# M115D.net
KiCad netlist of a schematic drawn in EAGLE
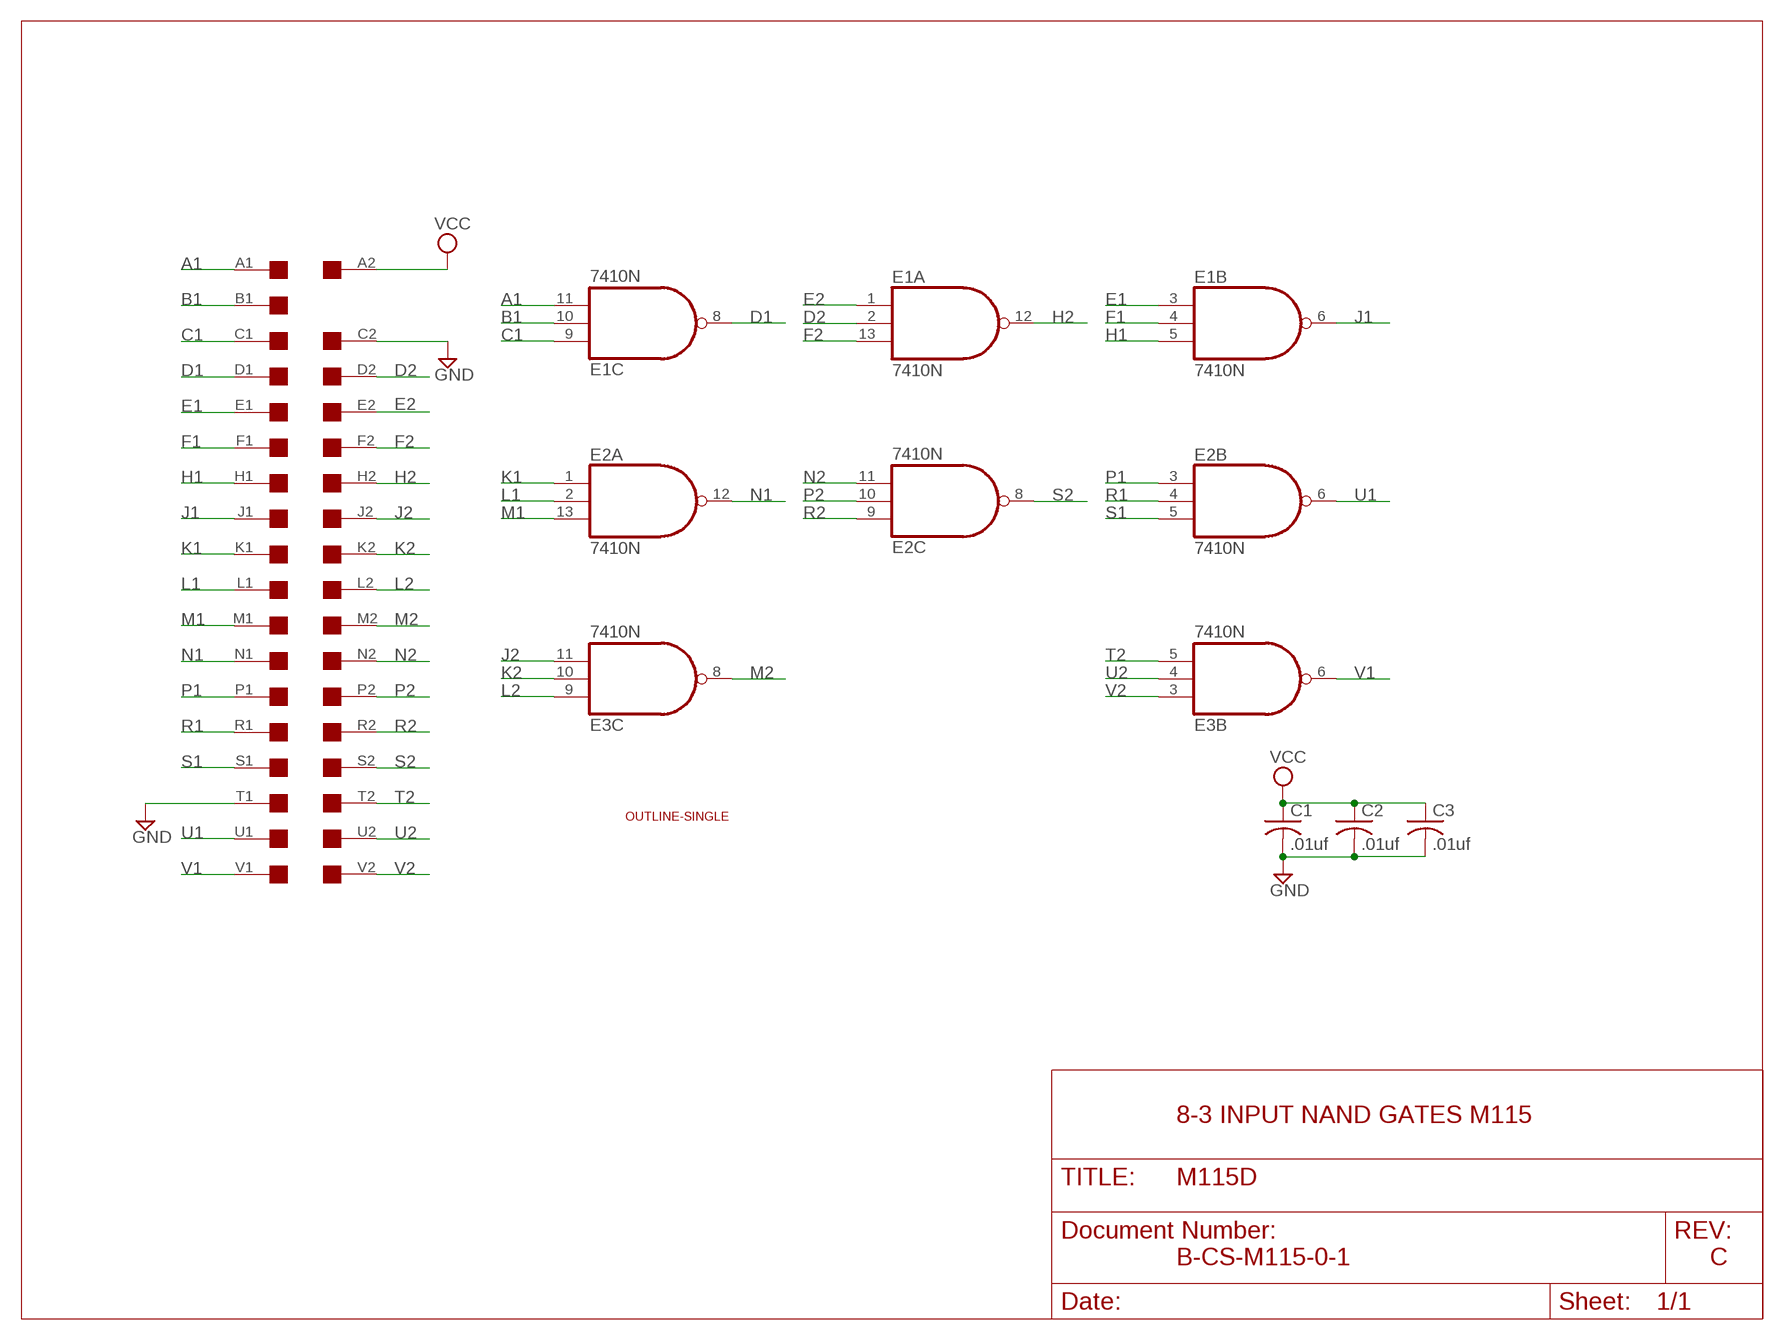
[diagram p0: schematic, sheet 1]

(export (version "E")
  (design (tool "Eeschema 10.0.6"))
  (components
    (comp (ref "C1")
      (value ".01uf")
      (footprint "eagle-import:C050-025X075")
      (libsource (lib "eagle-import") (part "C-US050-025X075"))
    )
    (comp (ref "C2")
      (value ".01uf")
      (footprint "eagle-import:C050-025X075")
      (libsource (lib "eagle-import") (part "C-US050-025X075"))
    )
    (comp (ref "C3")
      (value ".01uf")
      (footprint "eagle-import:C050-025X075")
      (libsource (lib "eagle-import") (part "C-US050-025X075"))
    )
    (comp (ref "E1")
      (value "7410N")
      (footprint "eagle-import:DIL14")
      (libsource (lib "eagle-import") (part "7410N"))
    )
    (comp (ref "E2")
      (value "7410N")
      (footprint "eagle-import:DIL14")
      (libsource (lib "eagle-import") (part "7410N"))
    )
    (comp (ref "E3")
      (value "7410N")
      (footprint "eagle-import:DIL14")
      (libsource (lib "eagle-import") (part "7410N"))
    )
    (comp (ref "U$1")
      (value "SINGLE")
      (footprint "eagle-import:EDGE-CON2")
      (libsource (lib "eagle-import") (part "SINGLE"))
    )
    (comp (ref "U$4")
      (value "OUTLINE-SINGLE")
      (footprint "eagle-import:SINGLE")
      (libsource (lib "eagle-import") (part "OUTLINE-SINGLE"))
    )
  )
  (nets
    (net (code "1") (name "/A1") (class "Default")
      (node (ref "E1") (pin "11") (pinfunction "I2_11") (pintype "input"))
      (node (ref "U$1") (pin "A1") (pinfunction "1_A1") (pintype "bidirectional"))
    )
    (net (code "2") (name "/B1") (class "Default")
      (node (ref "E1") (pin "10") (pinfunction "I1_10") (pintype "input"))
      (node (ref "U$1") (pin "B1") (pinfunction "1_B1") (pintype "bidirectional"))
    )
    (net (code "3") (name "/C1") (class "Default")
      (node (ref "E1") (pin "9") (pinfunction "I0_9") (pintype "input"))
      (node (ref "U$1") (pin "C1") (pinfunction "1_C1") (pintype "bidirectional"))
    )
    (net (code "4") (name "/D1") (class "Default")
      (node (ref "E1") (pin "8") (pinfunction "O_8") (pintype "output"))
      (node (ref "U$1") (pin "D1") (pinfunction "1_D1") (pintype "bidirectional"))
    )
    (net (code "5") (name "/D2") (class "Default")
      (node (ref "E1") (pin "2") (pinfunction "I1_2") (pintype "input"))
      (node (ref "U$1") (pin "D2") (pinfunction "1_D2") (pintype "bidirectional"))
    )
    (net (code "6") (name "/E1") (class "Default")
      (node (ref "E1") (pin "3") (pinfunction "I0_3") (pintype "input"))
      (node (ref "U$1") (pin "E1") (pinfunction "1_E1") (pintype "bidirectional"))
    )
    (net (code "7") (name "/E2") (class "Default")
      (node (ref "E1") (pin "1") (pinfunction "I0_1") (pintype "input"))
      (node (ref "U$1") (pin "E2") (pinfunction "1_E2") (pintype "bidirectional"))
    )
    (net (code "8") (name "/F1") (class "Default")
      (node (ref "E1") (pin "4") (pinfunction "I1_4") (pintype "input"))
      (node (ref "U$1") (pin "F1") (pinfunction "1_F1") (pintype "bidirectional"))
    )
    (net (code "9") (name "/F2") (class "Default")
      (node (ref "E1") (pin "13") (pinfunction "I2_13") (pintype "input"))
      (node (ref "U$1") (pin "F2") (pinfunction "1_F2") (pintype "bidirectional"))
    )
    (net (code "10") (name "/H1") (class "Default")
      (node (ref "E1") (pin "5") (pinfunction "I2_5") (pintype "input"))
      (node (ref "U$1") (pin "H1") (pinfunction "1_H1") (pintype "bidirectional"))
    )
    (net (code "11") (name "/H2") (class "Default")
      (node (ref "E1") (pin "12") (pinfunction "O_12") (pintype "output"))
      (node (ref "U$1") (pin "H2") (pinfunction "1_H2") (pintype "bidirectional"))
    )
    (net (code "12") (name "/J1") (class "Default")
      (node (ref "E1") (pin "6") (pinfunction "O_6") (pintype "output"))
      (node (ref "U$1") (pin "J1") (pinfunction "1_J1") (pintype "bidirectional"))
    )
    (net (code "13") (name "/J2") (class "Default")
      (node (ref "E3") (pin "11") (pinfunction "I2_11") (pintype "input"))
      (node (ref "U$1") (pin "J2") (pinfunction "1_J2") (pintype "bidirectional"))
    )
    (net (code "14") (name "/K1") (class "Default")
      (node (ref "E2") (pin "1") (pinfunction "I0_1") (pintype "input"))
      (node (ref "U$1") (pin "K1") (pinfunction "1_K1") (pintype "bidirectional"))
    )
    (net (code "15") (name "/K2") (class "Default")
      (node (ref "E3") (pin "10") (pinfunction "I1_10") (pintype "input"))
      (node (ref "U$1") (pin "K2") (pinfunction "1_K2") (pintype "bidirectional"))
    )
    (net (code "16") (name "/L1") (class "Default")
      (node (ref "E2") (pin "2") (pinfunction "I1_2") (pintype "input"))
      (node (ref "U$1") (pin "L1") (pinfunction "1_L1") (pintype "bidirectional"))
    )
    (net (code "17") (name "/L2") (class "Default")
      (node (ref "E3") (pin "9") (pinfunction "I0_9") (pintype "input"))
      (node (ref "U$1") (pin "L2") (pinfunction "1_L2") (pintype "bidirectional"))
    )
    (net (code "18") (name "/M1") (class "Default")
      (node (ref "E2") (pin "13") (pinfunction "I2_13") (pintype "input"))
      (node (ref "U$1") (pin "M1") (pinfunction "1_M1") (pintype "bidirectional"))
    )
    (net (code "19") (name "/M2") (class "Default")
      (node (ref "E3") (pin "8") (pinfunction "O_8") (pintype "output"))
      (node (ref "U$1") (pin "M2") (pinfunction "1_M2") (pintype "bidirectional"))
    )
    (net (code "20") (name "/N1") (class "Default")
      (node (ref "E2") (pin "12") (pinfunction "O_12") (pintype "output"))
      (node (ref "U$1") (pin "N1") (pinfunction "1_N1") (pintype "bidirectional"))
    )
    (net (code "21") (name "/N2") (class "Default")
      (node (ref "E2") (pin "11") (pinfunction "I2_11") (pintype "input"))
      (node (ref "U$1") (pin "N2") (pinfunction "1_N2") (pintype "bidirectional"))
    )
    (net (code "22") (name "/P1") (class "Default")
      (node (ref "E2") (pin "3") (pinfunction "I0_3") (pintype "input"))
      (node (ref "U$1") (pin "P1") (pinfunction "1_P1") (pintype "bidirectional"))
    )
    (net (code "23") (name "/P2") (class "Default")
      (node (ref "E2") (pin "10") (pinfunction "I1_10") (pintype "input"))
      (node (ref "U$1") (pin "P2") (pinfunction "1_P2") (pintype "bidirectional"))
    )
    (net (code "24") (name "/R1") (class "Default")
      (node (ref "E2") (pin "4") (pinfunction "I1_4") (pintype "input"))
      (node (ref "U$1") (pin "R1") (pinfunction "1_R1") (pintype "bidirectional"))
    )
    (net (code "25") (name "/R2") (class "Default")
      (node (ref "E2") (pin "9") (pinfunction "I0_9") (pintype "input"))
      (node (ref "U$1") (pin "R2") (pinfunction "1_R2") (pintype "bidirectional"))
    )
    (net (code "26") (name "/S1") (class "Default")
      (node (ref "E2") (pin "5") (pinfunction "I2_5") (pintype "input"))
      (node (ref "U$1") (pin "S1") (pinfunction "1_S1") (pintype "bidirectional"))
    )
    (net (code "27") (name "/S2") (class "Default")
      (node (ref "E2") (pin "8") (pinfunction "O_8") (pintype "output"))
      (node (ref "U$1") (pin "S2") (pinfunction "1_S2") (pintype "bidirectional"))
    )
    (net (code "28") (name "/T2") (class "Default")
      (node (ref "E3") (pin "5") (pinfunction "I2_5") (pintype "input"))
      (node (ref "U$1") (pin "T2") (pinfunction "1_T2") (pintype "bidirectional"))
    )
    (net (code "29") (name "/U1") (class "Default")
      (node (ref "E2") (pin "6") (pinfunction "O_6") (pintype "output"))
      (node (ref "U$1") (pin "U1") (pinfunction "1_U1") (pintype "bidirectional"))
    )
    (net (code "30") (name "/U2") (class "Default")
      (node (ref "E3") (pin "4") (pinfunction "I1_4") (pintype "input"))
      (node (ref "U$1") (pin "U2") (pinfunction "1_U2") (pintype "bidirectional"))
    )
    (net (code "31") (name "/V1") (class "Default")
      (node (ref "E3") (pin "6") (pinfunction "O_6") (pintype "output"))
      (node (ref "U$1") (pin "V1") (pinfunction "1_V1") (pintype "bidirectional"))
    )
    (net (code "32") (name "/V2") (class "Default")
      (node (ref "E3") (pin "3") (pinfunction "I0_3") (pintype "input"))
      (node (ref "U$1") (pin "V2") (pinfunction "1_V2") (pintype "bidirectional"))
    )
    (net (code "33") (name "GND") (class "Default")
      (node (ref "C1") (pin "2") (pinfunction "2_2") (pintype "passive"))
      (node (ref "C2") (pin "2") (pinfunction "2_2") (pintype "passive"))
      (node (ref "C3") (pin "2") (pinfunction "2_2") (pintype "passive"))
      (node (ref "U$1") (pin "C2") (pinfunction "1_C2") (pintype "bidirectional"))
      (node (ref "U$1") (pin "T1") (pinfunction "1_T1") (pintype "bidirectional"))
    )
    (net (code "34") (name "VCC") (class "Default")
      (node (ref "C1") (pin "1") (pinfunction "1_1") (pintype "passive"))
      (node (ref "C2") (pin "1") (pinfunction "1_1") (pintype "passive"))
      (node (ref "C3") (pin "1") (pinfunction "1_1") (pintype "passive"))
      (node (ref "U$1") (pin "A2") (pinfunction "1_A2") (pintype "bidirectional"))
    )
  )
)
